# GrrCON-Badge-Rev1.net
KiCad netlist of a schematic drawn in EAGLE
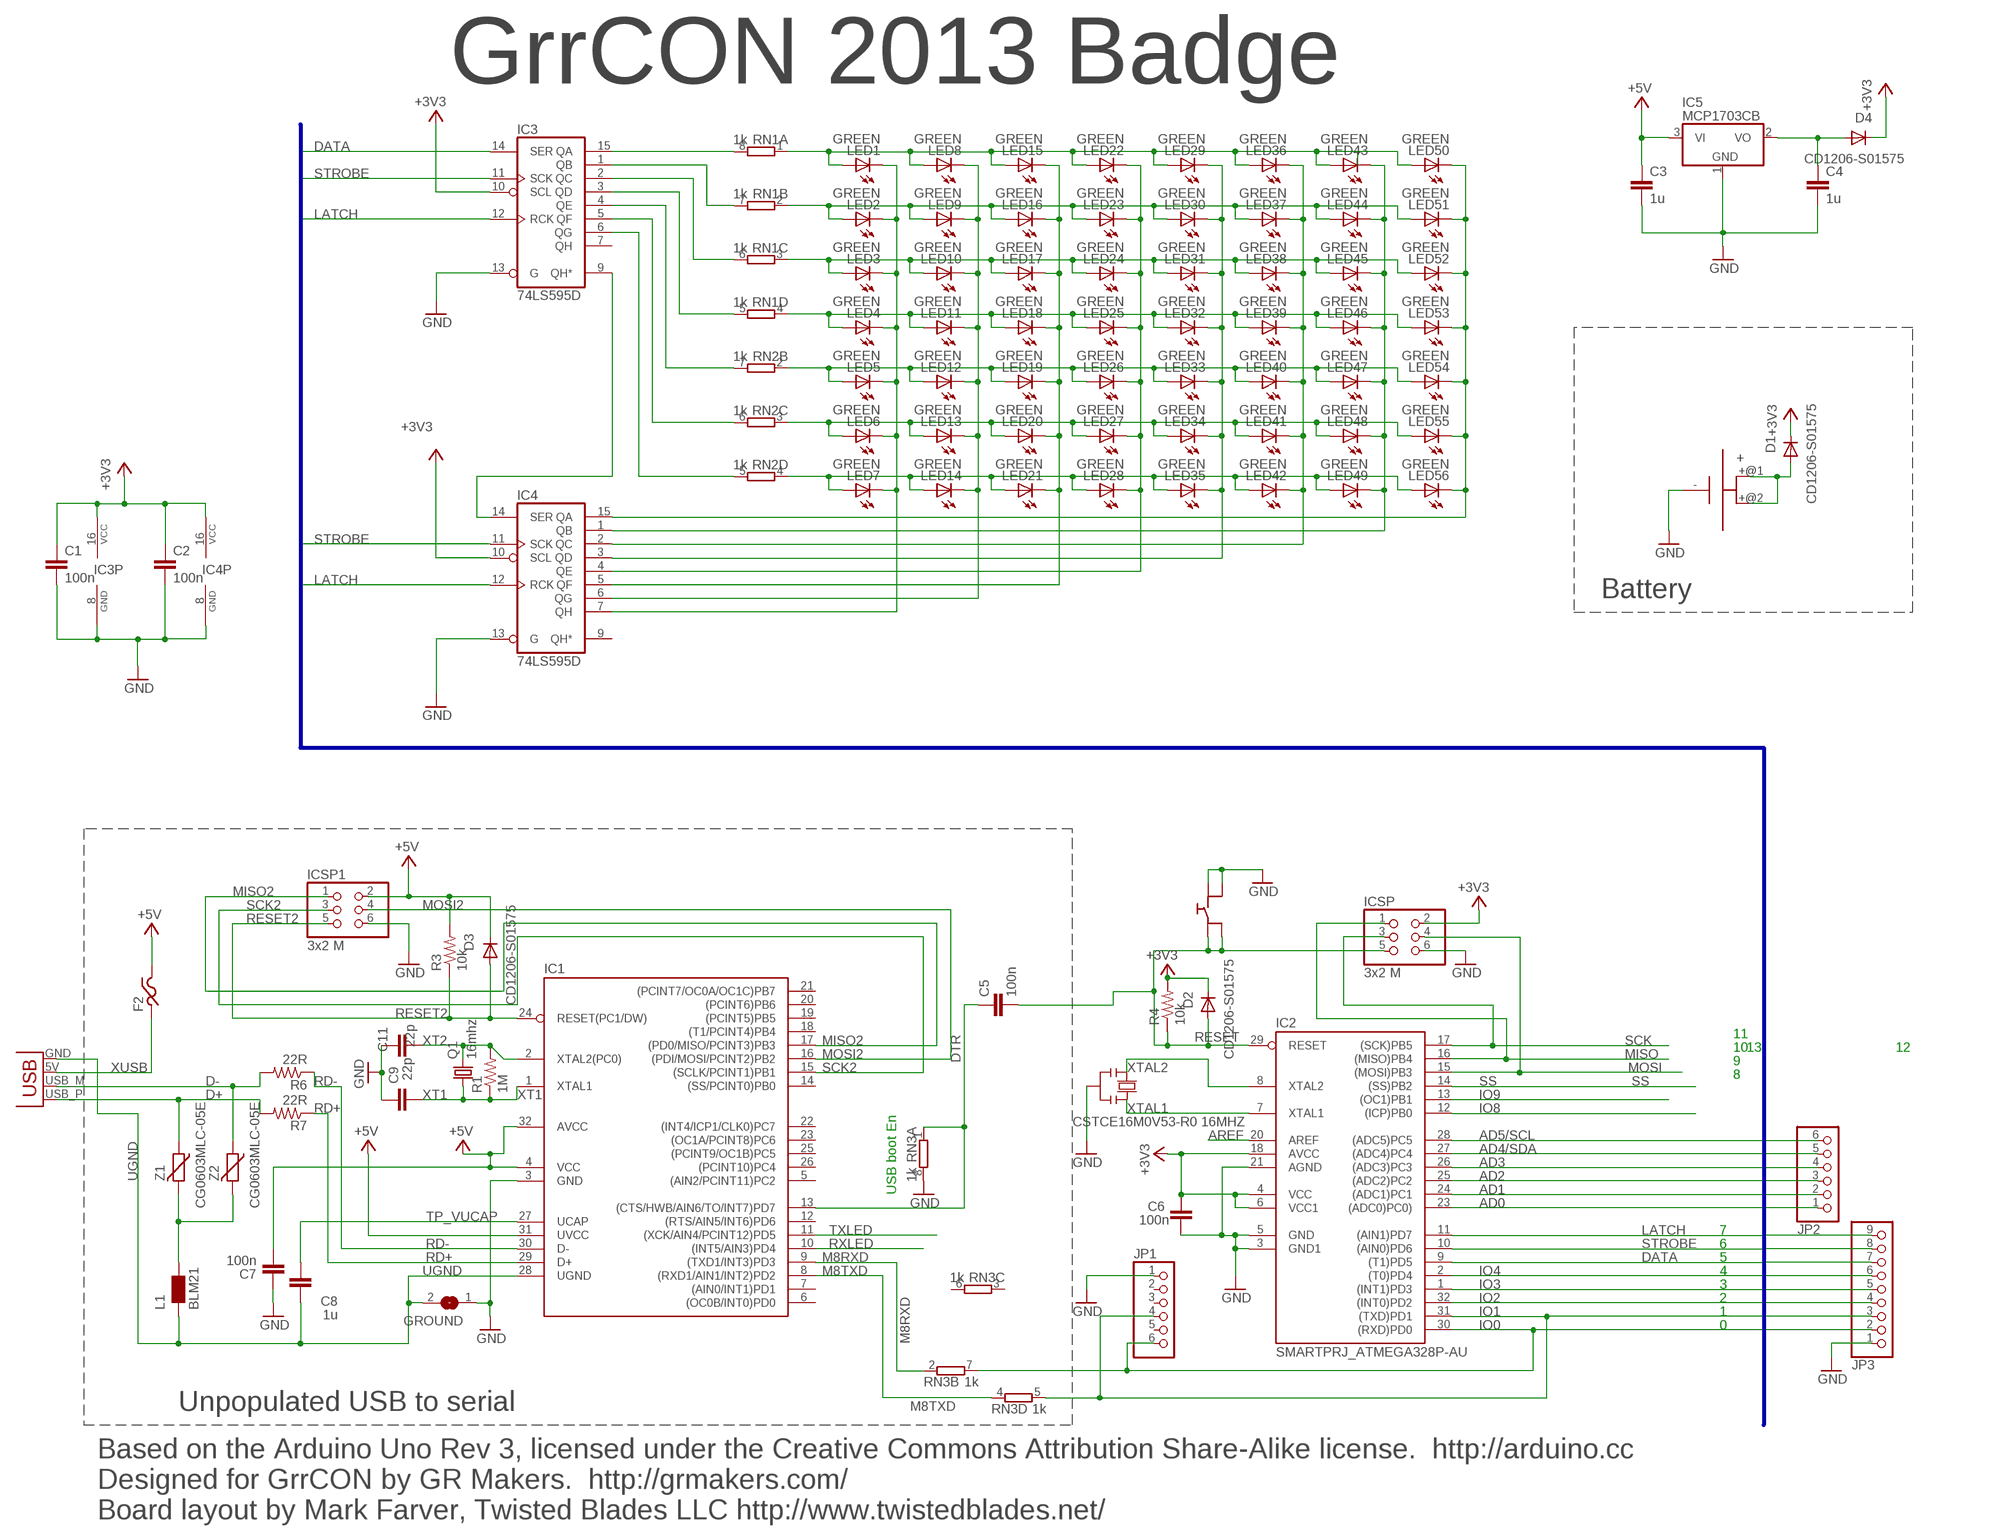
[diagram p0: schematic, sheet 1]

(export (version "E")
  (design (tool "Eeschema 10.0.6"))
  (components
    (comp (ref "B1")
      (value "KEYSTONE_COIN2450")
      (footprint "eagle-import:3009")
      (libsource (lib "eagle-import") (part "KEYSTONE_COIN2450"))
    )
    (comp (ref "C1")
      (value "100n")
      (footprint "eagle-import:C0805")
      (libsource (lib "eagle-import") (part "C-EUC0805"))
    )
    (comp (ref "C2")
      (value "100n")
      (footprint "eagle-import:C0805")
      (libsource (lib "eagle-import") (part "C-EUC0805"))
    )
    (comp (ref "C3")
      (value "1u")
      (footprint "eagle-import:C0805")
      (libsource (lib "eagle-import") (part "C-EUC0805"))
    )
    (comp (ref "C4")
      (value "1u")
      (footprint "eagle-import:C0805")
      (libsource (lib "eagle-import") (part "C-EUC0805"))
    )
    (comp (ref "C5")
      (value "100n")
      (footprint "eagle-import:C0805")
      (libsource (lib "eagle-import") (part "C-EUC0805"))
    )
    (comp (ref "C6")
      (value "100n")
      (footprint "eagle-import:C0805")
      (libsource (lib "eagle-import") (part "C-EUC0805"))
    )
    (comp (ref "C7")
      (value "100n")
      (footprint "eagle-import:C0805")
      (libsource (lib "eagle-import") (part "C-EUC0805"))
    )
    (comp (ref "C8")
      (value "1u")
      (footprint "eagle-import:C0805")
      (libsource (lib "eagle-import") (part "C-EUC0805"))
    )
    (comp (ref "C9")
      (value "22p")
      (footprint "eagle-import:C0805")
      (libsource (lib "eagle-import") (part "C-EUC0805"))
    )
    (comp (ref "C11")
      (value "22p")
      (footprint "eagle-import:C0805")
      (libsource (lib "eagle-import") (part "C-EUC0805"))
    )
    (comp (ref "D1")
      (value "CD1206-S01575")
      (footprint "eagle-import:MINIMELF")
      (libsource (lib "eagle-import") (part "DIODE-MINIMELF"))
    )
    (comp (ref "D2")
      (value "CD1206-S01575")
      (footprint "eagle-import:MINIMELF")
      (libsource (lib "eagle-import") (part "DIODE-MINIMELF"))
    )
    (comp (ref "D3")
      (value "CD1206-S01575")
      (footprint "eagle-import:MINIMELF")
      (libsource (lib "eagle-import") (part "DIODE-MINIMELF"))
    )
    (comp (ref "D4")
      (value "CD1206-S01575")
      (footprint "eagle-import:MINIMELF")
      (libsource (lib "eagle-import") (part "DIODE-MINIMELF"))
    )
    (comp (ref "F2")
      (value "PTC-FUSE-US1206")
      (footprint "eagle-import:F1206")
      (libsource (lib "eagle-import") (part "PTC-FUSE-US1206"))
    )
    (comp (ref "GROUND")
      (value "SJ")
      (footprint "eagle-import:SJ")
      (libsource (lib "eagle-import") (part "SJ"))
    )
    (comp (ref "IC1")
      (value "ATMEGA16U2AU")
      (footprint "eagle-import:SMARTPRJ_TQFP32-08")
      (libsource (lib "eagle-import") (part "ATMEGA16U2AU"))
    )
    (comp (ref "IC2")
      (value "SMARTPRJ_ATMEGA328P-AU")
      (footprint "eagle-import:SMARTPRJ_TQFP32-08")
      (libsource (lib "eagle-import") (part "SMARTPRJ_ATMEGA328P-AU"))
    )
    (comp (ref "IC3")
      (value "74LS595D")
      (footprint "eagle-import:SO16")
      (libsource (lib "eagle-import") (part "74595DLS"))
    )
    (comp (ref "IC4")
      (value "74LS595D")
      (footprint "eagle-import:SO16")
      (libsource (lib "eagle-import") (part "74595DLS"))
    )
    (comp (ref "IC5")
      (value "MCP1703CB")
      (footprint "eagle-import:SOT23")
      (libsource (lib "eagle-import") (part "MCP1703CB"))
    )
    (comp (ref "ICSP")
      (value "3x2 M")
      (footprint "eagle-import:2X03")
      (libsource (lib "eagle-import") (part "PINHD-2X3"))
    )
    (comp (ref "ICSP1")
      (value "3x2 M")
      (footprint "eagle-import:2X03")
      (libsource (lib "eagle-import") (part "PINHD-2X3"))
    )
    (comp (ref "JP1")
      (value "PINHD-1X6")
      (footprint "eagle-import:1X06")
      (libsource (lib "eagle-import") (part "PINHD-1X6"))
    )
    (comp (ref "JP2")
      (value "PINHD-1X6")
      (footprint "eagle-import:1X06")
      (libsource (lib "eagle-import") (part "PINHD-1X6"))
    )
    (comp (ref "JP3")
      (value "PINHD-1X9")
      (footprint "eagle-import:1X09")
      (libsource (lib "eagle-import") (part "PINHD-1X9"))
    )
    (comp (ref "L1")
      (value "BLM21")
      (footprint "eagle-import:0805")
      (libsource (lib "eagle-import") (part "WE-CBF_0805"))
    )
    (comp (ref "LED1")
      (value "GREEN")
      (footprint "eagle-import:CHIPLED_0603")
      (libsource (lib "eagle-import") (part "LEDCHIPLED_0603"))
    )
    (comp (ref "LED2")
      (value "GREEN")
      (footprint "eagle-import:CHIPLED_0603")
      (libsource (lib "eagle-import") (part "LEDCHIPLED_0603"))
    )
    (comp (ref "LED3")
      (value "GREEN")
      (footprint "eagle-import:CHIPLED_0603")
      (libsource (lib "eagle-import") (part "LEDCHIPLED_0603"))
    )
    (comp (ref "LED4")
      (value "GREEN")
      (footprint "eagle-import:CHIPLED_0603")
      (libsource (lib "eagle-import") (part "LEDCHIPLED_0603"))
    )
    (comp (ref "LED5")
      (value "GREEN")
      (footprint "eagle-import:CHIPLED_0603")
      (libsource (lib "eagle-import") (part "LEDCHIPLED_0603"))
    )
    (comp (ref "LED6")
      (value "GREEN")
      (footprint "eagle-import:CHIPLED_0603")
      (libsource (lib "eagle-import") (part "LEDCHIPLED_0603"))
    )
    (comp (ref "LED7")
      (value "GREEN")
      (footprint "eagle-import:CHIPLED_0603")
      (libsource (lib "eagle-import") (part "LEDCHIPLED_0603"))
    )
    (comp (ref "LED8")
      (value "GREEN")
      (footprint "eagle-import:CHIPLED_0603")
      (libsource (lib "eagle-import") (part "LEDCHIPLED_0603"))
    )
    (comp (ref "LED9")
      (value "GREEN")
      (footprint "eagle-import:CHIPLED_0603")
      (libsource (lib "eagle-import") (part "LEDCHIPLED_0603"))
    )
    (comp (ref "LED10")
      (value "GREEN")
      (footprint "eagle-import:CHIPLED_0603")
      (libsource (lib "eagle-import") (part "LEDCHIPLED_0603"))
    )
    (comp (ref "LED11")
      (value "GREEN")
      (footprint "eagle-import:CHIPLED_0603")
      (libsource (lib "eagle-import") (part "LEDCHIPLED_0603"))
    )
    (comp (ref "LED12")
      (value "GREEN")
      (footprint "eagle-import:CHIPLED_0603")
      (libsource (lib "eagle-import") (part "LEDCHIPLED_0603"))
    )
    (comp (ref "LED13")
      (value "GREEN")
      (footprint "eagle-import:CHIPLED_0603")
      (libsource (lib "eagle-import") (part "LEDCHIPLED_0603"))
    )
    (comp (ref "LED14")
      (value "GREEN")
      (footprint "eagle-import:CHIPLED_0603")
      (libsource (lib "eagle-import") (part "LEDCHIPLED_0603"))
    )
    (comp (ref "LED15")
      (value "GREEN")
      (footprint "eagle-import:CHIPLED_0603")
      (libsource (lib "eagle-import") (part "LEDCHIPLED_0603"))
    )
    (comp (ref "LED16")
      (value "GREEN")
      (footprint "eagle-import:CHIPLED_0603")
      (libsource (lib "eagle-import") (part "LEDCHIPLED_0603"))
    )
    (comp (ref "LED17")
      (value "GREEN")
      (footprint "eagle-import:CHIPLED_0603")
      (libsource (lib "eagle-import") (part "LEDCHIPLED_0603"))
    )
    (comp (ref "LED18")
      (value "GREEN")
      (footprint "eagle-import:CHIPLED_0603")
      (libsource (lib "eagle-import") (part "LEDCHIPLED_0603"))
    )
    (comp (ref "LED19")
      (value "GREEN")
      (footprint "eagle-import:CHIPLED_0603")
      (libsource (lib "eagle-import") (part "LEDCHIPLED_0603"))
    )
    (comp (ref "LED20")
      (value "GREEN")
      (footprint "eagle-import:CHIPLED_0603")
      (libsource (lib "eagle-import") (part "LEDCHIPLED_0603"))
    )
    (comp (ref "LED21")
      (value "GREEN")
      (footprint "eagle-import:CHIPLED_0603")
      (libsource (lib "eagle-import") (part "LEDCHIPLED_0603"))
    )
    (comp (ref "LED22")
      (value "GREEN")
      (footprint "eagle-import:CHIPLED_0603")
      (libsource (lib "eagle-import") (part "LEDCHIPLED_0603"))
    )
    (comp (ref "LED23")
      (value "GREEN")
      (footprint "eagle-import:CHIPLED_0603")
      (libsource (lib "eagle-import") (part "LEDCHIPLED_0603"))
    )
    (comp (ref "LED24")
      (value "GREEN")
      (footprint "eagle-import:CHIPLED_0603")
      (libsource (lib "eagle-import") (part "LEDCHIPLED_0603"))
    )
    (comp (ref "LED25")
      (value "GREEN")
      (footprint "eagle-import:CHIPLED_0603")
      (libsource (lib "eagle-import") (part "LEDCHIPLED_0603"))
    )
    (comp (ref "LED26")
      (value "GREEN")
      (footprint "eagle-import:CHIPLED_0603")
      (libsource (lib "eagle-import") (part "LEDCHIPLED_0603"))
    )
    (comp (ref "LED27")
      (value "GREEN")
      (footprint "eagle-import:CHIPLED_0603")
      (libsource (lib "eagle-import") (part "LEDCHIPLED_0603"))
    )
    (comp (ref "LED28")
      (value "GREEN")
      (footprint "eagle-import:CHIPLED_0603")
      (libsource (lib "eagle-import") (part "LEDCHIPLED_0603"))
    )
    (comp (ref "LED29")
      (value "GREEN")
      (footprint "eagle-import:CHIPLED_0603")
      (libsource (lib "eagle-import") (part "LEDCHIPLED_0603"))
    )
    (comp (ref "LED30")
      (value "GREEN")
      (footprint "eagle-import:CHIPLED_0603")
      (libsource (lib "eagle-import") (part "LEDCHIPLED_0603"))
    )
    (comp (ref "LED31")
      (value "GREEN")
      (footprint "eagle-import:CHIPLED_0603")
      (libsource (lib "eagle-import") (part "LEDCHIPLED_0603"))
    )
    (comp (ref "LED32")
      (value "GREEN")
      (footprint "eagle-import:CHIPLED_0603")
      (libsource (lib "eagle-import") (part "LEDCHIPLED_0603"))
    )
    (comp (ref "LED33")
      (value "GREEN")
      (footprint "eagle-import:CHIPLED_0603")
      (libsource (lib "eagle-import") (part "LEDCHIPLED_0603"))
    )
    (comp (ref "LED34")
      (value "GREEN")
      (footprint "eagle-import:CHIPLED_0603")
      (libsource (lib "eagle-import") (part "LEDCHIPLED_0603"))
    )
    (comp (ref "LED35")
      (value "GREEN")
      (footprint "eagle-import:CHIPLED_0603")
      (libsource (lib "eagle-import") (part "LEDCHIPLED_0603"))
    )
    (comp (ref "LED36")
      (value "GREEN")
      (footprint "eagle-import:CHIPLED_0603")
      (libsource (lib "eagle-import") (part "LEDCHIPLED_0603"))
    )
    (comp (ref "LED37")
      (value "GREEN")
      (footprint "eagle-import:CHIPLED_0603")
      (libsource (lib "eagle-import") (part "LEDCHIPLED_0603"))
    )
    (comp (ref "LED38")
      (value "GREEN")
      (footprint "eagle-import:CHIPLED_0603")
      (libsource (lib "eagle-import") (part "LEDCHIPLED_0603"))
    )
    (comp (ref "LED39")
      (value "GREEN")
      (footprint "eagle-import:CHIPLED_0603")
      (libsource (lib "eagle-import") (part "LEDCHIPLED_0603"))
    )
    (comp (ref "LED40")
      (value "GREEN")
      (footprint "eagle-import:CHIPLED_0603")
      (libsource (lib "eagle-import") (part "LEDCHIPLED_0603"))
    )
    (comp (ref "LED41")
      (value "GREEN")
      (footprint "eagle-import:CHIPLED_0603")
      (libsource (lib "eagle-import") (part "LEDCHIPLED_0603"))
    )
    (comp (ref "LED42")
      (value "GREEN")
      (footprint "eagle-import:CHIPLED_0603")
      (libsource (lib "eagle-import") (part "LEDCHIPLED_0603"))
    )
    (comp (ref "LED43")
      (value "GREEN")
      (footprint "eagle-import:CHIPLED_0603")
      (libsource (lib "eagle-import") (part "LEDCHIPLED_0603"))
    )
    (comp (ref "LED44")
      (value "GREEN")
      (footprint "eagle-import:CHIPLED_0603")
      (libsource (lib "eagle-import") (part "LEDCHIPLED_0603"))
    )
    (comp (ref "LED45")
      (value "GREEN")
      (footprint "eagle-import:CHIPLED_0603")
      (libsource (lib "eagle-import") (part "LEDCHIPLED_0603"))
    )
    (comp (ref "LED46")
      (value "GREEN")
      (footprint "eagle-import:CHIPLED_0603")
      (libsource (lib "eagle-import") (part "LEDCHIPLED_0603"))
    )
    (comp (ref "LED47")
      (value "GREEN")
      (footprint "eagle-import:CHIPLED_0603")
      (libsource (lib "eagle-import") (part "LEDCHIPLED_0603"))
    )
    (comp (ref "LED48")
      (value "GREEN")
      (footprint "eagle-import:CHIPLED_0603")
      (libsource (lib "eagle-import") (part "LEDCHIPLED_0603"))
    )
    (comp (ref "LED49")
      (value "GREEN")
      (footprint "eagle-import:CHIPLED_0603")
      (libsource (lib "eagle-import") (part "LEDCHIPLED_0603"))
    )
    (comp (ref "LED50")
      (value "GREEN")
      (footprint "eagle-import:CHIPLED_0603")
      (libsource (lib "eagle-import") (part "LEDCHIPLED_0603"))
    )
    (comp (ref "LED51")
      (value "GREEN")
      (footprint "eagle-import:CHIPLED_0603")
      (libsource (lib "eagle-import") (part "LEDCHIPLED_0603"))
    )
    (comp (ref "LED52")
      (value "GREEN")
      (footprint "eagle-import:CHIPLED_0603")
      (libsource (lib "eagle-import") (part "LEDCHIPLED_0603"))
    )
    (comp (ref "LED53")
      (value "GREEN")
      (footprint "eagle-import:CHIPLED_0603")
      (libsource (lib "eagle-import") (part "LEDCHIPLED_0603"))
    )
    (comp (ref "LED54")
      (value "GREEN")
      (footprint "eagle-import:CHIPLED_0603")
      (libsource (lib "eagle-import") (part "LEDCHIPLED_0603"))
    )
    (comp (ref "LED55")
      (value "GREEN")
      (footprint "eagle-import:CHIPLED_0603")
      (libsource (lib "eagle-import") (part "LEDCHIPLED_0603"))
    )
    (comp (ref "LED56")
      (value "GREEN")
      (footprint "eagle-import:CHIPLED_0603")
      (libsource (lib "eagle-import") (part "LEDCHIPLED_0603"))
    )
    (comp (ref "Q1")
      (value "16mhz")
      (footprint "eagle-import:SM49")
      (libsource (lib "eagle-import") (part "CRYSTALSM49"))
    )
    (comp (ref "R1")
      (value "1M")
      (footprint "eagle-import:R0805")
      (libsource (lib "eagle-import") (part "R-US_R0805"))
    )
    (comp (ref "R3")
      (value "10k")
      (footprint "eagle-import:R0805")
      (libsource (lib "eagle-import") (part "R-US_R0805"))
    )
    (comp (ref "R4")
      (value "10k")
      (footprint "eagle-import:R0805")
      (libsource (lib "eagle-import") (part "R-US_R0805"))
    )
    (comp (ref "R6")
      (value "22R")
      (footprint "eagle-import:R0805")
      (libsource (lib "eagle-import") (part "R-US_R0805"))
    )
    (comp (ref "R7")
      (value "22R")
      (footprint "eagle-import:R0805")
      (libsource (lib "eagle-import") (part "R-US_R0805"))
    )
    (comp (ref "RN1")
      (value "1k")
      (footprint "eagle-import:RESISTOR-DIL_CAY16")
      (libsource (lib "eagle-import") (part "RESISTOR-DIL_4R-NCAY16"))
    )
    (comp (ref "RN2")
      (value "1k")
      (footprint "eagle-import:RESISTOR-DIL_CAY16")
      (libsource (lib "eagle-import") (part "RESISTOR-DIL_4R-NCAY16"))
    )
    (comp (ref "RN3")
      (value "1k")
      (footprint "eagle-import:RESISTOR-DIL_CAY16")
      (libsource (lib "eagle-import") (part "RESISTOR-DIL_4R-NCAY16"))
    )
    (comp (ref "SW1")
      (value "PTS645SMT")
      (footprint "eagle-import:PTS645SMT")
      (libsource (lib "eagle-import") (part "PTS645SMT"))
    )
    (comp (ref "X1")
      (value "USBPCB")
      (footprint "eagle-import:USB-A-PCB")
      (libsource (lib "eagle-import") (part "USBPCB"))
    )
    (comp (ref "Y2")
      (value "CSTCE16M0V53-R0 16MHZ")
      (footprint "eagle-import:RESONATOR")
      (libsource (lib "eagle-import") (part "RESONATORMU"))
    )
    (comp (ref "Z1")
      (value "CG0603MLC-05E")
      (footprint "eagle-import:CT_CN0603")
      (libsource (lib "eagle-import") (part "VARISTORCN0603"))
    )
    (comp (ref "Z2")
      (value "CG0603MLC-05E")
      (footprint "eagle-import:CT_CN0603")
      (libsource (lib "eagle-import") (part "VARISTORCN0603"))
    )
  )
  (nets
    (net (code "1") (name "+3V3") (class "Default")
      (node (ref "C1") (pin "1") (pinfunction "1_1") (pintype "passive"))
      (node (ref "C2") (pin "1") (pinfunction "1_1") (pintype "passive"))
      (node (ref "C6") (pin "2") (pinfunction "2_2") (pintype "passive"))
      (node (ref "D1") (pin "C") (pinfunction "C_C") (pintype "passive"))
      (node (ref "D2") (pin "C") (pinfunction "C_C") (pintype "passive"))
      (node (ref "D4") (pin "C") (pinfunction "C_C") (pintype "passive"))
      (node (ref "IC2") (pin "18") (pinfunction "AVCC_18") (pintype "power_in"))
      (node (ref "IC2") (pin "4") (pinfunction "VCC_4") (pintype "power_in"))
      (node (ref "IC2") (pin "6") (pinfunction "VCC1_6") (pintype "power_in"))
      (node (ref "IC3") (pin "10") (pinfunction "SCL_10") (pintype "input"))
      (node (ref "IC3") (pin "16") (pinfunction "VCC_16") (pintype "power_in"))
      (node (ref "IC4") (pin "10") (pinfunction "SCL_10") (pintype "input"))
      (node (ref "IC4") (pin "16") (pinfunction "VCC_16") (pintype "power_in"))
      (node (ref "ICSP") (pin "2") (pinfunction "2_2") (pintype "passive"))
      (node (ref "R4") (pin "2") (pinfunction "2_2") (pintype "passive"))
    )
    (net (code "2") (name "+5V") (class "Default")
      (node (ref "C3") (pin "1") (pinfunction "1_1") (pintype "passive"))
      (node (ref "C7") (pin "1") (pinfunction "1_1") (pintype "passive"))
      (node (ref "D3") (pin "C") (pinfunction "C_C") (pintype "passive"))
      (node (ref "F2") (pin "2") (pinfunction "2_2") (pintype "passive"))
      (node (ref "IC1") (pin "31") (pinfunction "UVCC_31") (pintype "power_in"))
      (node (ref "IC1") (pin "32") (pinfunction "AVCC_32") (pintype "power_in"))
      (node (ref "IC1") (pin "4") (pinfunction "VCC_4") (pintype "power_in"))
      (node (ref "IC5") (pin "3") (pinfunction "VI_3") (pintype "input"))
      (node (ref "ICSP1") (pin "2") (pinfunction "2_2") (pintype "passive"))
      (node (ref "R3") (pin "2") (pinfunction "2_2") (pintype "passive"))
    )
    (net (code "3") (name "/AD0") (class "Default")
      (node (ref "IC2") (pin "23") (pinfunction "(ADC0)PC0)_23") (pintype "bidirectional"))
      (node (ref "JP2") (pin "1") (pinfunction "1_1") (pintype "passive"))
    )
    (net (code "4") (name "/AD1") (class "Default")
      (node (ref "IC2") (pin "24") (pinfunction "(ADC1)PC1_24") (pintype "bidirectional"))
      (node (ref "JP2") (pin "2") (pinfunction "2_2") (pintype "passive"))
    )
    (net (code "5") (name "/AD2") (class "Default")
      (node (ref "IC2") (pin "25") (pinfunction "(ADC2)PC2_25") (pintype "bidirectional"))
      (node (ref "JP2") (pin "3") (pinfunction "3_3") (pintype "passive"))
    )
    (net (code "6") (name "/AD3") (class "Default")
      (node (ref "IC2") (pin "26") (pinfunction "(ADC3)PC3_26") (pintype "bidirectional"))
      (node (ref "JP2") (pin "4") (pinfunction "4_4") (pintype "passive"))
    )
    (net (code "7") (name "/AD4{slash}SDA") (class "Default")
      (node (ref "IC2") (pin "27") (pinfunction "(ADC4)PC4_27") (pintype "bidirectional"))
      (node (ref "JP2") (pin "5") (pinfunction "5_5") (pintype "passive"))
    )
    (net (code "8") (name "/AD5{slash}SCL") (class "Default")
      (node (ref "IC2") (pin "28") (pinfunction "(ADC5)PC5_28") (pintype "bidirectional"))
      (node (ref "JP2") (pin "6") (pinfunction "6_6") (pintype "passive"))
    )
    (net (code "9") (name "/AREF") (class "Default")
      (node (ref "IC2") (pin "20") (pinfunction "AREF_20") (pintype "passive"))
    )
    (net (code "10") (name "/D+") (class "Default")
      (node (ref "R7") (pin "2") (pinfunction "2_2") (pintype "passive"))
      (node (ref "X1") (pin "USB_P") (pinfunction "D+_USB_P") (pintype "bidirectional"))
      (node (ref "Z1") (pin "1") (pinfunction "1_1") (pintype "passive"))
    )
    (net (code "11") (name "/D-") (class "Default")
      (node (ref "R6") (pin "2") (pinfunction "2_2") (pintype "passive"))
      (node (ref "X1") (pin "USB_M") (pinfunction "D-_USB_M") (pintype "bidirectional"))
      (node (ref "Z2") (pin "1") (pinfunction "1_1") (pintype "passive"))
    )
    (net (code "12") (name "/DATA") (class "Default")
      (node (ref "IC2") (pin "9") (pinfunction "(T1)PD5_9") (pintype "bidirectional"))
      (node (ref "IC3") (pin "14") (pinfunction "SER_14") (pintype "input"))
      (node (ref "JP3") (pin "7") (pinfunction "7_7") (pintype "passive"))
    )
    (net (code "13") (name "/DTR") (class "Default")
      (node (ref "C5") (pin "1") (pinfunction "1_1") (pintype "passive"))
      (node (ref "IC1") (pin "13") (pinfunction "(CTS/HWB/AIN6/TO/INT7)PD7_13") (pintype "bidirectional"))
      (node (ref "RN3") (pin "1") (pinfunction "1_1") (pintype "passive"))
    )
    (net (code "14") (name "/IO0") (class "Default")
      (node (ref "IC2") (pin "30") (pinfunction "(RXD)PD0_30") (pintype "bidirectional"))
      (node (ref "JP1") (pin "6") (pinfunction "6_6") (pintype "passive"))
      (node (ref "JP3") (pin "2") (pinfunction "2_2") (pintype "passive"))
      (node (ref "RN3") (pin "7") (pinfunction "2_7") (pintype "passive"))
    )
    (net (code "15") (name "/IO1") (class "Default")
      (node (ref "IC2") (pin "31") (pinfunction "(TXD)PD1_31") (pintype "bidirectional"))
      (node (ref "JP1") (pin "4") (pinfunction "4_4") (pintype "passive"))
      (node (ref "JP3") (pin "3") (pinfunction "3_3") (pintype "passive"))
      (node (ref "RN3") (pin "5") (pinfunction "2_5") (pintype "passive"))
    )
    (net (code "16") (name "/IO2") (class "Default")
      (node (ref "IC2") (pin "32") (pinfunction "(INT0)PD2_32") (pintype "bidirectional"))
      (node (ref "JP3") (pin "4") (pinfunction "4_4") (pintype "passive"))
    )
    (net (code "17") (name "/IO3") (class "Default")
      (node (ref "IC2") (pin "1") (pinfunction "(INT1)PD3_1") (pintype "bidirectional"))
      (node (ref "JP3") (pin "5") (pinfunction "5_5") (pintype "passive"))
    )
    (net (code "18") (name "/IO4") (class "Default")
      (node (ref "IC2") (pin "2") (pinfunction "(T0)PD4_2") (pintype "bidirectional"))
      (node (ref "JP3") (pin "6") (pinfunction "6_6") (pintype "passive"))
    )
    (net (code "19") (name "/IO8") (class "Default")
      (node (ref "IC2") (pin "12") (pinfunction "(ICP)PB0_12") (pintype "bidirectional"))
    )
    (net (code "20") (name "/IO9") (class "Default")
      (node (ref "IC2") (pin "13") (pinfunction "(OC1)PB1_13") (pintype "bidirectional"))
    )
    (net (code "21") (name "/LATCH") (class "Default")
      (node (ref "IC2") (pin "11") (pinfunction "(AIN1)PD7_11") (pintype "bidirectional"))
      (node (ref "IC3") (pin "12") (pinfunction "RCK_12") (pintype "input"))
      (node (ref "IC4") (pin "12") (pinfunction "RCK_12") (pintype "input"))
      (node (ref "JP3") (pin "9") (pinfunction "9_9") (pintype "passive"))
    )
    (net (code "22") (name "/M8RXD") (class "Default")
      (node (ref "IC1") (pin "9") (pinfunction "(TXD1/INT3)PD3_9") (pintype "bidirectional"))
      (node (ref "RN3") (pin "2") (pinfunction "1_2") (pintype "passive"))
    )
    (net (code "23") (name "/M8TXD") (class "Default")
      (node (ref "IC1") (pin "8") (pinfunction "(RXD1/AIN1/INT2)PD2_8") (pintype "bidirectional"))
      (node (ref "RN3") (pin "4") (pinfunction "1_4") (pintype "passive"))
    )
    (net (code "24") (name "/MISO") (class "Default")
      (node (ref "IC2") (pin "16") (pinfunction "(MISO)PB4_16") (pintype "bidirectional"))
      (node (ref "ICSP") (pin "1") (pinfunction "1_1") (pintype "passive"))
    )
    (net (code "25") (name "/MISO2") (class "Default")
      (node (ref "IC1") (pin "17") (pinfunction "(PD0/MISO/PCINT3)PB3_17") (pintype "bidirectional"))
      (node (ref "ICSP1") (pin "1") (pinfunction "1_1") (pintype "passive"))
    )
    (net (code "26") (name "/MOSI") (class "Default")
      (node (ref "IC2") (pin "15") (pinfunction "(MOSI)PB3_15") (pintype "bidirectional"))
      (node (ref "ICSP") (pin "4") (pinfunction "4_4") (pintype "passive"))
    )
    (net (code "27") (name "/MOSI2") (class "Default")
      (node (ref "IC1") (pin "16") (pinfunction "(PDI/MOSI/PCINT2)PB2_16") (pintype "bidirectional"))
      (node (ref "ICSP1") (pin "4") (pinfunction "4_4") (pintype "passive"))
    )
    (net (code "28") (name "/RD+") (class "Default")
      (node (ref "IC1") (pin "29") (pinfunction "D+_29") (pintype "bidirectional"))
      (node (ref "R7") (pin "1") (pinfunction "1_1") (pintype "passive"))
    )
    (net (code "29") (name "/RD-") (class "Default")
      (node (ref "IC1") (pin "30") (pinfunction "D-_30") (pintype "bidirectional"))
      (node (ref "R6") (pin "1") (pinfunction "1_1") (pintype "passive"))
    )
    (net (code "30") (name "/RESET") (class "Default")
      (node (ref "C5") (pin "2") (pinfunction "2_2") (pintype "passive"))
      (node (ref "D2") (pin "A") (pinfunction "A_A") (pintype "passive"))
      (node (ref "IC2") (pin "29") (pinfunction "RESET_29") (pintype "input"))
      (node (ref "ICSP") (pin "5") (pinfunction "5_5") (pintype "passive"))
      (node (ref "R4") (pin "1") (pinfunction "1_1") (pintype "passive"))
      (node (ref "SW1") (pin "1A") (pinfunction "1A_1A") (pintype "bidirectional"))
      (node (ref "SW1") (pin "1B") (pinfunction "1B_1B") (pintype "bidirectional"))
    )
    (net (code "31") (name "/RESET2") (class "Default")
      (node (ref "D3") (pin "A") (pinfunction "A_A") (pintype "passive"))
      (node (ref "IC1") (pin "24") (pinfunction "RESET(PC1/DW)_24") (pintype "input"))
      (node (ref "ICSP1") (pin "5") (pinfunction "5_5") (pintype "passive"))
      (node (ref "R3") (pin "1") (pinfunction "1_1") (pintype "passive"))
    )
    (net (code "32") (name "/RXLED") (class "Default")
      (node (ref "IC1") (pin "10") (pinfunction "(INT5/AIN3)PD4_10") (pintype "bidirectional"))
    )
    (net (code "33") (name "/SCK") (class "Default")
      (node (ref "IC2") (pin "17") (pinfunction "(SCK)PB5_17") (pintype "bidirectional"))
      (node (ref "ICSP") (pin "3") (pinfunction "3_3") (pintype "passive"))
    )
    (net (code "34") (name "/SCK2") (class "Default")
      (node (ref "IC1") (pin "15") (pinfunction "(SCLK/PCINT1)PB1_15") (pintype "bidirectional"))
      (node (ref "ICSP1") (pin "3") (pinfunction "3_3") (pintype "passive"))
    )
    (net (code "35") (name "/SS") (class "Default")
      (node (ref "IC2") (pin "14") (pinfunction "(SS)PB2_14") (pintype "bidirectional"))
    )
    (net (code "36") (name "/STROBE") (class "Default")
      (node (ref "IC2") (pin "10") (pinfunction "(AIN0)PD6_10") (pintype "bidirectional"))
      (node (ref "IC3") (pin "11") (pinfunction "SCK_11") (pintype "input"))
      (node (ref "IC4") (pin "11") (pinfunction "SCK_11") (pintype "input"))
      (node (ref "JP3") (pin "8") (pinfunction "8_8") (pintype "passive"))
    )
    (net (code "37") (name "/TP_VUCAP") (class "Default")
      (node (ref "C8") (pin "1") (pinfunction "1_1") (pintype "passive"))
      (node (ref "IC1") (pin "27") (pinfunction "UCAP_27") (pintype "passive"))
    )
    (net (code "38") (name "/TXLED") (class "Default")
      (node (ref "IC1") (pin "11") (pinfunction "(XCK/AIN4/PCINT12)PD5_11") (pintype "bidirectional"))
    )
    (net (code "39") (name "/UGND") (class "Default")
      (node (ref "C8") (pin "2") (pinfunction "2_2") (pintype "passive"))
      (node (ref "GROUND") (pin "2") (pinfunction "2_2") (pintype "passive"))
      (node (ref "IC1") (pin "28") (pinfunction "UGND_28") (pintype "power_in"))
      (node (ref "L1") (pin "1") (pinfunction "1_1") (pintype "passive"))
      (node (ref "X1") (pin "GND") (pinfunction "GND_GND") (pintype "bidirectional"))
    )
    (net (code "40") (name "/XT1") (class "Default")
      (node (ref "C9") (pin "1") (pinfunction "1_1") (pintype "passive"))
      (node (ref "IC1") (pin "1") (pinfunction "XTAL1_1") (pintype "bidirectional"))
      (node (ref "Q1") (pin "1") (pinfunction "1_1") (pintype "passive"))
      (node (ref "R1") (pin "1") (pinfunction "1_1") (pintype "passive"))
    )
    (net (code "41") (name "/XT2") (class "Default")
      (node (ref "C11") (pin "1") (pinfunction "1_1") (pintype "passive"))
      (node (ref "IC1") (pin "2") (pinfunction "XTAL2(PC0)_2") (pintype "bidirectional"))
      (node (ref "Q1") (pin "2") (pinfunction "2_2") (pintype "passive"))
      (node (ref "R1") (pin "2") (pinfunction "2_2") (pintype "passive"))
    )
    (net (code "42") (name "/XTAL1") (class "Default")
      (node (ref "IC2") (pin "7") (pinfunction "XTAL1_7") (pintype "bidirectional"))
      (node (ref "Y2") (pin "3") (pinfunction "3_3") (pintype "passive"))
    )
    (net (code "43") (name "/XTAL2") (class "Default")
      (node (ref "IC2") (pin "8") (pinfunction "XTAL2_8") (pintype "bidirectional"))
      (node (ref "Y2") (pin "1") (pinfunction "1_1") (pintype "passive"))
    )
    (net (code "44") (name "/XUSB") (class "Default")
      (node (ref "F2") (pin "1") (pinfunction "1_1") (pintype "passive"))
      (node (ref "X1") (pin "5V") (pinfunction "VBUS_5V") (pintype "bidirectional"))
    )
    (net (code "45") (name "GND") (class "Default")
      (node (ref "B1") (pin "-") (pinfunction "-_-") (pintype "power_in"))
      (node (ref "C1") (pin "2") (pinfunction "2_2") (pintype "passive"))
      (node (ref "C11") (pin "2") (pinfunction "2_2") (pintype "passive"))
      (node (ref "C2") (pin "2") (pinfunction "2_2") (pintype "passive"))
      (node (ref "C3") (pin "2") (pinfunction "2_2") (pintype "passive"))
      (node (ref "C4") (pin "2") (pinfunction "2_2") (pintype "passive"))
      (node (ref "C6") (pin "1") (pinfunction "1_1") (pintype "passive"))
      (node (ref "C7") (pin "2") (pinfunction "2_2") (pintype "passive"))
      (node (ref "C9") (pin "2") (pinfunction "2_2") (pintype "passive"))
      (node (ref "GROUND") (pin "1") (pinfunction "1_1") (pintype "passive"))
      (node (ref "IC1") (pin "3") (pinfunction "GND_3") (pintype "power_in"))
      (node (ref "IC2") (pin "21") (pinfunction "AGND_21") (pintype "power_in"))
      (node (ref "IC2") (pin "3") (pinfunction "GND1_3") (pintype "power_in"))
      (node (ref "IC2") (pin "5") (pinfunction "GND_5") (pintype "power_in"))
      (node (ref "IC3") (pin "13") (pinfunction "G_13") (pintype "input"))
      (node (ref "IC3") (pin "8") (pinfunction "GND_8") (pintype "power_in"))
      (node (ref "IC4") (pin "13") (pinfunction "G_13") (pintype "input"))
      (node (ref "IC4") (pin "8") (pinfunction "GND_8") (pintype "power_in"))
      (node (ref "IC5") (pin "1") (pinfunction "GND_1") (pintype "passive"))
      (node (ref "ICSP") (pin "6") (pinfunction "6_6") (pintype "passive"))
      (node (ref "ICSP1") (pin "6") (pinfunction "6_6") (pintype "passive"))
      (node (ref "JP1") (pin "1") (pinfunction "1_1") (pintype "passive"))
      (node (ref "JP3") (pin "1") (pinfunction "1_1") (pintype "passive"))
      (node (ref "RN3") (pin "8") (pinfunction "2_8") (pintype "passive"))
      (node (ref "SW1") (pin "2A") (pinfunction "2A_2A") (pintype "bidirectional"))
      (node (ref "SW1") (pin "2B") (pinfunction "2B_2B") (pintype "bidirectional"))
      (node (ref "Y2") (pin "2") (pinfunction "2_2") (pintype "passive"))
    )
    (net (code "46") (name "Net-(B1-+-Pad+@1)") (class "Default")
      (node (ref "B1") (pin "+@1") (pinfunction "+_+@1") (pintype "power_in"))
      (node (ref "B1") (pin "+@2") (pinfunction "+_+@2") (pintype "power_in"))
      (node (ref "D1") (pin "A") (pinfunction "A_A") (pintype "passive"))
    )
    (net (code "47") (name "Net-(IC3A-QA)") (class "Default")
      (node (ref "IC3") (pin "15") (pinfunction "QA_15") (pintype "tri_state"))
      (node (ref "RN1") (pin "8") (pinfunction "2_8") (pintype "passive"))
    )
    (net (code "48") (name "Net-(IC3A-QB)") (class "Default")
      (node (ref "IC3") (pin "1") (pinfunction "QB_1") (pintype "tri_state"))
      (node (ref "RN1") (pin "7") (pinfunction "2_7") (pintype "passive"))
    )
    (net (code "49") (name "Net-(IC3A-QC)") (class "Default")
      (node (ref "IC3") (pin "2") (pinfunction "QC_2") (pintype "tri_state"))
      (node (ref "RN1") (pin "6") (pinfunction "2_6") (pintype "passive"))
    )
    (net (code "50") (name "Net-(IC3A-QD)") (class "Default")
      (node (ref "IC3") (pin "3") (pinfunction "QD_3") (pintype "tri_state"))
      (node (ref "RN1") (pin "5") (pinfunction "2_5") (pintype "passive"))
    )
    (net (code "51") (name "Net-(IC3A-QE)") (class "Default")
      (node (ref "IC3") (pin "4") (pinfunction "QE_4") (pintype "tri_state"))
      (node (ref "RN2") (pin "7") (pinfunction "2_7") (pintype "passive"))
    )
    (net (code "52") (name "Net-(IC3A-QF)") (class "Default")
      (node (ref "IC3") (pin "5") (pinfunction "QF_5") (pintype "tri_state"))
      (node (ref "RN2") (pin "6") (pinfunction "2_6") (pintype "passive"))
    )
    (net (code "53") (name "Net-(IC3A-QG)") (class "Default")
      (node (ref "IC3") (pin "6") (pinfunction "QG_6") (pintype "tri_state"))
      (node (ref "RN2") (pin "5") (pinfunction "2_5") (pintype "passive"))
    )
    (net (code "54") (name "Net-(IC3A-QH*)") (class "Default")
      (node (ref "IC3") (pin "9") (pinfunction "QH*_9") (pintype "tri_state"))
      (node (ref "IC4") (pin "14") (pinfunction "SER_14") (pintype "input"))
    )
    (net (code "55") (name "Net-(IC4A-QA)") (class "Default")
      (node (ref "IC4") (pin "15") (pinfunction "QA_15") (pintype "tri_state"))
      (node (ref "LED50") (pin "C") (pinfunction "C_C") (pintype "passive"))
      (node (ref "LED51") (pin "C") (pinfunction "C_C") (pintype "passive"))
      (node (ref "LED52") (pin "C") (pinfunction "C_C") (pintype "passive"))
      (node (ref "LED53") (pin "C") (pinfunction "C_C") (pintype "passive"))
      (node (ref "LED54") (pin "C") (pinfunction "C_C") (pintype "passive"))
      (node (ref "LED55") (pin "C") (pinfunction "C_C") (pintype "passive"))
      (node (ref "LED56") (pin "C") (pinfunction "C_C") (pintype "passive"))
    )
    (net (code "56") (name "Net-(IC4A-QB)") (class "Default")
      (node (ref "IC4") (pin "1") (pinfunction "QB_1") (pintype "tri_state"))
      (node (ref "LED43") (pin "C") (pinfunction "C_C") (pintype "passive"))
      (node (ref "LED44") (pin "C") (pinfunction "C_C") (pintype "passive"))
      (node (ref "LED45") (pin "C") (pinfunction "C_C") (pintype "passive"))
      (node (ref "LED46") (pin "C") (pinfunction "C_C") (pintype "passive"))
      (node (ref "LED47") (pin "C") (pinfunction "C_C") (pintype "passive"))
      (node (ref "LED48") (pin "C") (pinfunction "C_C") (pintype "passive"))
      (node (ref "LED49") (pin "C") (pinfunction "C_C") (pintype "passive"))
    )
    (net (code "57") (name "Net-(IC4A-QC)") (class "Default")
      (node (ref "IC4") (pin "2") (pinfunction "QC_2") (pintype "tri_state"))
      (node (ref "LED36") (pin "C") (pinfunction "C_C") (pintype "passive"))
      (node (ref "LED37") (pin "C") (pinfunction "C_C") (pintype "passive"))
      (node (ref "LED38") (pin "C") (pinfunction "C_C") (pintype "passive"))
      (node (ref "LED39") (pin "C") (pinfunction "C_C") (pintype "passive"))
      (node (ref "LED40") (pin "C") (pinfunction "C_C") (pintype "passive"))
      (node (ref "LED41") (pin "C") (pinfunction "C_C") (pintype "passive"))
      (node (ref "LED42") (pin "C") (pinfunction "C_C") (pintype "passive"))
    )
    (net (code "58") (name "Net-(IC4A-QD)") (class "Default")
      (node (ref "IC4") (pin "3") (pinfunction "QD_3") (pintype "tri_state"))
      (node (ref "LED29") (pin "C") (pinfunction "C_C") (pintype "passive"))
      (node (ref "LED30") (pin "C") (pinfunction "C_C") (pintype "passive"))
      (node (ref "LED31") (pin "C") (pinfunction "C_C") (pintype "passive"))
      (node (ref "LED32") (pin "C") (pinfunction "C_C") (pintype "passive"))
      (node (ref "LED33") (pin "C") (pinfunction "C_C") (pintype "passive"))
      (node (ref "LED34") (pin "C") (pinfunction "C_C") (pintype "passive"))
      (node (ref "LED35") (pin "C") (pinfunction "C_C") (pintype "passive"))
    )
    (net (code "59") (name "Net-(IC4A-QE)") (class "Default")
      (node (ref "IC4") (pin "4") (pinfunction "QE_4") (pintype "tri_state"))
      (node (ref "LED22") (pin "C") (pinfunction "C_C") (pintype "passive"))
      (node (ref "LED23") (pin "C") (pinfunction "C_C") (pintype "passive"))
      (node (ref "LED24") (pin "C") (pinfunction "C_C") (pintype "passive"))
      (node (ref "LED25") (pin "C") (pinfunction "C_C") (pintype "passive"))
      (node (ref "LED26") (pin "C") (pinfunction "C_C") (pintype "passive"))
      (node (ref "LED27") (pin "C") (pinfunction "C_C") (pintype "passive"))
      (node (ref "LED28") (pin "C") (pinfunction "C_C") (pintype "passive"))
    )
    (net (code "60") (name "Net-(IC4A-QF)") (class "Default")
      (node (ref "IC4") (pin "5") (pinfunction "QF_5") (pintype "tri_state"))
      (node (ref "LED15") (pin "C") (pinfunction "C_C") (pintype "passive"))
      (node (ref "LED16") (pin "C") (pinfunction "C_C") (pintype "passive"))
      (node (ref "LED17") (pin "C") (pinfunction "C_C") (pintype "passive"))
      (node (ref "LED18") (pin "C") (pinfunction "C_C") (pintype "passive"))
      (node (ref "LED19") (pin "C") (pinfunction "C_C") (pintype "passive"))
      (node (ref "LED20") (pin "C") (pinfunction "C_C") (pintype "passive"))
      (node (ref "LED21") (pin "C") (pinfunction "C_C") (pintype "passive"))
    )
    (net (code "61") (name "Net-(IC4A-QG)") (class "Default")
      (node (ref "IC4") (pin "6") (pinfunction "QG_6") (pintype "tri_state"))
      (node (ref "LED10") (pin "C") (pinfunction "C_C") (pintype "passive"))
      (node (ref "LED11") (pin "C") (pinfunction "C_C") (pintype "passive"))
      (node (ref "LED12") (pin "C") (pinfunction "C_C") (pintype "passive"))
      (node (ref "LED13") (pin "C") (pinfunction "C_C") (pintype "passive"))
      (node (ref "LED14") (pin "C") (pinfunction "C_C") (pintype "passive"))
      (node (ref "LED8") (pin "C") (pinfunction "C_C") (pintype "passive"))
      (node (ref "LED9") (pin "C") (pinfunction "C_C") (pintype "passive"))
    )
    (net (code "62") (name "Net-(IC4A-QH)") (class "Default")
      (node (ref "IC4") (pin "7") (pinfunction "QH_7") (pintype "tri_state"))
      (node (ref "LED1") (pin "C") (pinfunction "C_C") (pintype "passive"))
      (node (ref "LED2") (pin "C") (pinfunction "C_C") (pintype "passive"))
      (node (ref "LED3") (pin "C") (pinfunction "C_C") (pintype "passive"))
      (node (ref "LED4") (pin "C") (pinfunction "C_C") (pintype "passive"))
      (node (ref "LED5") (pin "C") (pinfunction "C_C") (pintype "passive"))
      (node (ref "LED6") (pin "C") (pinfunction "C_C") (pintype "passive"))
      (node (ref "LED7") (pin "C") (pinfunction "C_C") (pintype "passive"))
    )
    (net (code "63") (name "Net-(IC5-VO)") (class "Default")
      (node (ref "C4") (pin "1") (pinfunction "1_1") (pintype "passive"))
      (node (ref "D4") (pin "A") (pinfunction "A_A") (pintype "passive"))
      (node (ref "IC5") (pin "2") (pinfunction "VO_2") (pintype "passive"))
    )
    (net (code "64") (name "Net-(L1-Pad2)") (class "Default")
      (node (ref "L1") (pin "2") (pinfunction "2_2") (pintype "passive"))
      (node (ref "Z1") (pin "2") (pinfunction "2_2") (pintype "passive"))
      (node (ref "Z2") (pin "2") (pinfunction "2_2") (pintype "passive"))
    )
    (net (code "65") (name "Net-(LED1-PadA)") (class "Default")
      (node (ref "LED1") (pin "A") (pinfunction "A_A") (pintype "passive"))
      (node (ref "LED15") (pin "A") (pinfunction "A_A") (pintype "passive"))
      (node (ref "LED22") (pin "A") (pinfunction "A_A") (pintype "passive"))
      (node (ref "LED29") (pin "A") (pinfunction "A_A") (pintype "passive"))
      (node (ref "LED36") (pin "A") (pinfunction "A_A") (pintype "passive"))
      (node (ref "LED43") (pin "A") (pinfunction "A_A") (pintype "passive"))
      (node (ref "LED50") (pin "A") (pinfunction "A_A") (pintype "passive"))
      (node (ref "LED8") (pin "A") (pinfunction "A_A") (pintype "passive"))
      (node (ref "RN1") (pin "1") (pinfunction "1_1") (pintype "passive"))
    )
    (net (code "66") (name "Net-(RN1B-1)") (class "Default")
      (node (ref "LED16") (pin "A") (pinfunction "A_A") (pintype "passive"))
      (node (ref "LED2") (pin "A") (pinfunction "A_A") (pintype "passive"))
      (node (ref "LED23") (pin "A") (pinfunction "A_A") (pintype "passive"))
      (node (ref "LED30") (pin "A") (pinfunction "A_A") (pintype "passive"))
      (node (ref "LED37") (pin "A") (pinfunction "A_A") (pintype "passive"))
      (node (ref "LED44") (pin "A") (pinfunction "A_A") (pintype "passive"))
      (node (ref "LED51") (pin "A") (pinfunction "A_A") (pintype "passive"))
      (node (ref "LED9") (pin "A") (pinfunction "A_A") (pintype "passive"))
      (node (ref "RN1") (pin "2") (pinfunction "1_2") (pintype "passive"))
    )
    (net (code "67") (name "Net-(RN1C-1)") (class "Default")
      (node (ref "LED10") (pin "A") (pinfunction "A_A") (pintype "passive"))
      (node (ref "LED17") (pin "A") (pinfunction "A_A") (pintype "passive"))
      (node (ref "LED24") (pin "A") (pinfunction "A_A") (pintype "passive"))
      (node (ref "LED3") (pin "A") (pinfunction "A_A") (pintype "passive"))
      (node (ref "LED31") (pin "A") (pinfunction "A_A") (pintype "passive"))
      (node (ref "LED38") (pin "A") (pinfunction "A_A") (pintype "passive"))
      (node (ref "LED45") (pin "A") (pinfunction "A_A") (pintype "passive"))
      (node (ref "LED52") (pin "A") (pinfunction "A_A") (pintype "passive"))
      (node (ref "RN1") (pin "3") (pinfunction "1_3") (pintype "passive"))
    )
    (net (code "68") (name "Net-(RN1D-1)") (class "Default")
      (node (ref "LED11") (pin "A") (pinfunction "A_A") (pintype "passive"))
      (node (ref "LED18") (pin "A") (pinfunction "A_A") (pintype "passive"))
      (node (ref "LED25") (pin "A") (pinfunction "A_A") (pintype "passive"))
      (node (ref "LED32") (pin "A") (pinfunction "A_A") (pintype "passive"))
      (node (ref "LED39") (pin "A") (pinfunction "A_A") (pintype "passive"))
      (node (ref "LED4") (pin "A") (pinfunction "A_A") (pintype "passive"))
      (node (ref "LED46") (pin "A") (pinfunction "A_A") (pintype "passive"))
      (node (ref "LED53") (pin "A") (pinfunction "A_A") (pintype "passive"))
      (node (ref "RN1") (pin "4") (pinfunction "1_4") (pintype "passive"))
    )
    (net (code "69") (name "Net-(RN2B-1)") (class "Default")
      (node (ref "LED12") (pin "A") (pinfunction "A_A") (pintype "passive"))
      (node (ref "LED19") (pin "A") (pinfunction "A_A") (pintype "passive"))
      (node (ref "LED26") (pin "A") (pinfunction "A_A") (pintype "passive"))
      (node (ref "LED33") (pin "A") (pinfunction "A_A") (pintype "passive"))
      (node (ref "LED40") (pin "A") (pinfunction "A_A") (pintype "passive"))
      (node (ref "LED47") (pin "A") (pinfunction "A_A") (pintype "passive"))
      (node (ref "LED5") (pin "A") (pinfunction "A_A") (pintype "passive"))
      (node (ref "LED54") (pin "A") (pinfunction "A_A") (pintype "passive"))
      (node (ref "RN2") (pin "2") (pinfunction "1_2") (pintype "passive"))
    )
    (net (code "70") (name "Net-(RN2C-1)") (class "Default")
      (node (ref "LED13") (pin "A") (pinfunction "A_A") (pintype "passive"))
      (node (ref "LED20") (pin "A") (pinfunction "A_A") (pintype "passive"))
      (node (ref "LED27") (pin "A") (pinfunction "A_A") (pintype "passive"))
      (node (ref "LED34") (pin "A") (pinfunction "A_A") (pintype "passive"))
      (node (ref "LED41") (pin "A") (pinfunction "A_A") (pintype "passive"))
      (node (ref "LED48") (pin "A") (pinfunction "A_A") (pintype "passive"))
      (node (ref "LED55") (pin "A") (pinfunction "A_A") (pintype "passive"))
      (node (ref "LED6") (pin "A") (pinfunction "A_A") (pintype "passive"))
      (node (ref "RN2") (pin "3") (pinfunction "1_3") (pintype "passive"))
    )
    (net (code "71") (name "Net-(RN2D-1)") (class "Default")
      (node (ref "LED14") (pin "A") (pinfunction "A_A") (pintype "passive"))
      (node (ref "LED21") (pin "A") (pinfunction "A_A") (pintype "passive"))
      (node (ref "LED28") (pin "A") (pinfunction "A_A") (pintype "passive"))
      (node (ref "LED35") (pin "A") (pinfunction "A_A") (pintype "passive"))
      (node (ref "LED42") (pin "A") (pinfunction "A_A") (pintype "passive"))
      (node (ref "LED49") (pin "A") (pinfunction "A_A") (pintype "passive"))
      (node (ref "LED56") (pin "A") (pinfunction "A_A") (pintype "passive"))
      (node (ref "LED7") (pin "A") (pinfunction "A_A") (pintype "passive"))
      (node (ref "RN2") (pin "4") (pinfunction "1_4") (pintype "passive"))
    )
    (net (code "72") (name "unconnected-(IC1-(AIN0{slash}INT1)PD1-Pad7)") (class "Default")
      (node (ref "IC1") (pin "7") (pinfunction "(AIN0/INT1)PD1_7") (pintype "bidirectional"))
    )
    (net (code "73") (name "unconnected-(IC1-(AIN2{slash}PCINT11)PC2-Pad5)") (class "Default")
      (node (ref "IC1") (pin "5") (pinfunction "(AIN2/PCINT11)PC2_5") (pintype "bidirectional"))
    )
    (net (code "74") (name "unconnected-(IC1-(INT4{slash}ICP1{slash}CLK0)PC7-Pad22)") (class "Default")
      (node (ref "IC1") (pin "22") (pinfunction "(INT4/ICP1/CLK0)PC7_22") (pintype "bidirectional"))
    )
    (net (code "75") (name "unconnected-(IC1-(OC0B{slash}INT0)PD0-Pad6)") (class "Default")
      (node (ref "IC1") (pin "6") (pinfunction "(OC0B/INT0)PD0_6") (pintype "bidirectional"))
    )
    (net (code "76") (name "unconnected-(IC1-(OC1A{slash}PCINT8)PC6-Pad23)") (class "Default")
      (node (ref "IC1") (pin "23") (pinfunction "(OC1A/PCINT8)PC6_23") (pintype "bidirectional"))
    )
    (net (code "77") (name "unconnected-(IC1-(PCINT5)PB5-Pad19)") (class "Default")
      (node (ref "IC1") (pin "19") (pinfunction "(PCINT5)PB5_19") (pintype "bidirectional"))
    )
    (net (code "78") (name "unconnected-(IC1-(PCINT6)PB6-Pad20)") (class "Default")
      (node (ref "IC1") (pin "20") (pinfunction "(PCINT6)PB6_20") (pintype "bidirectional"))
    )
    (net (code "79") (name "unconnected-(IC1-(PCINT7{slash}OC0A{slash}OC1C)PB7-Pad21)") (class "Default")
      (node (ref "IC1") (pin "21") (pinfunction "(PCINT7/OC0A/OC1C)PB7_21") (pintype "bidirectional"))
    )
    (net (code "80") (name "unconnected-(IC1-(PCINT9{slash}OC1B)PC5-Pad25)") (class "Default")
      (node (ref "IC1") (pin "25") (pinfunction "(PCINT9/OC1B)PC5_25") (pintype "bidirectional"))
    )
    (net (code "81") (name "unconnected-(IC1-(PCINT10)PC4-Pad26)") (class "Default")
      (node (ref "IC1") (pin "26") (pinfunction "(PCINT10)PC4_26") (pintype "bidirectional"))
    )
    (net (code "82") (name "unconnected-(IC1-(RTS{slash}AIN5{slash}INT6)PD6-Pad12)") (class "Default")
      (node (ref "IC1") (pin "12") (pinfunction "(RTS/AIN5/INT6)PD6_12") (pintype "bidirectional"))
    )
    (net (code "83") (name "unconnected-(IC1-(SS{slash}PCINT0)PB0-Pad14)") (class "Default")
      (node (ref "IC1") (pin "14") (pinfunction "(SS/PCINT0)PB0_14") (pintype "bidirectional"))
    )
    (net (code "84") (name "unconnected-(IC1-(T1{slash}PCINT4)PB4-Pad18)") (class "Default")
      (node (ref "IC1") (pin "18") (pinfunction "(T1/PCINT4)PB4_18") (pintype "bidirectional"))
    )
    (net (code "85") (name "unconnected-(IC3A-QH-Pad7)") (class "Default")
      (node (ref "IC3") (pin "7") (pinfunction "QH_7") (pintype "tri_state"))
    )
    (net (code "86") (name "unconnected-(IC4A-QH*-Pad9)") (class "Default")
      (node (ref "IC4") (pin "9") (pinfunction "QH*_9") (pintype "tri_state"))
    )
    (net (code "87") (name "unconnected-(JP1-Pad2)") (class "Default")
      (node (ref "JP1") (pin "2") (pinfunction "2_2") (pintype "passive"))
    )
    (net (code "88") (name "unconnected-(JP1-Pad3)") (class "Default")
      (node (ref "JP1") (pin "3") (pinfunction "3_3") (pintype "passive"))
    )
    (net (code "89") (name "unconnected-(JP1-Pad5)") (class "Default")
      (node (ref "JP1") (pin "5") (pinfunction "5_5") (pintype "passive"))
    )
    (net (code "90") (name "unconnected-(RN3C-1-Pad3)") (class "Default")
      (node (ref "RN3") (pin "3") (pinfunction "1_3") (pintype "passive"))
    )
    (net (code "91") (name "unconnected-(RN3C-2-Pad6)") (class "Default")
      (node (ref "RN3") (pin "6") (pinfunction "2_6") (pintype "passive"))
    )
  )
)
